# SOL_R2.net
KiCad netlist of a schematic drawn in EAGLE
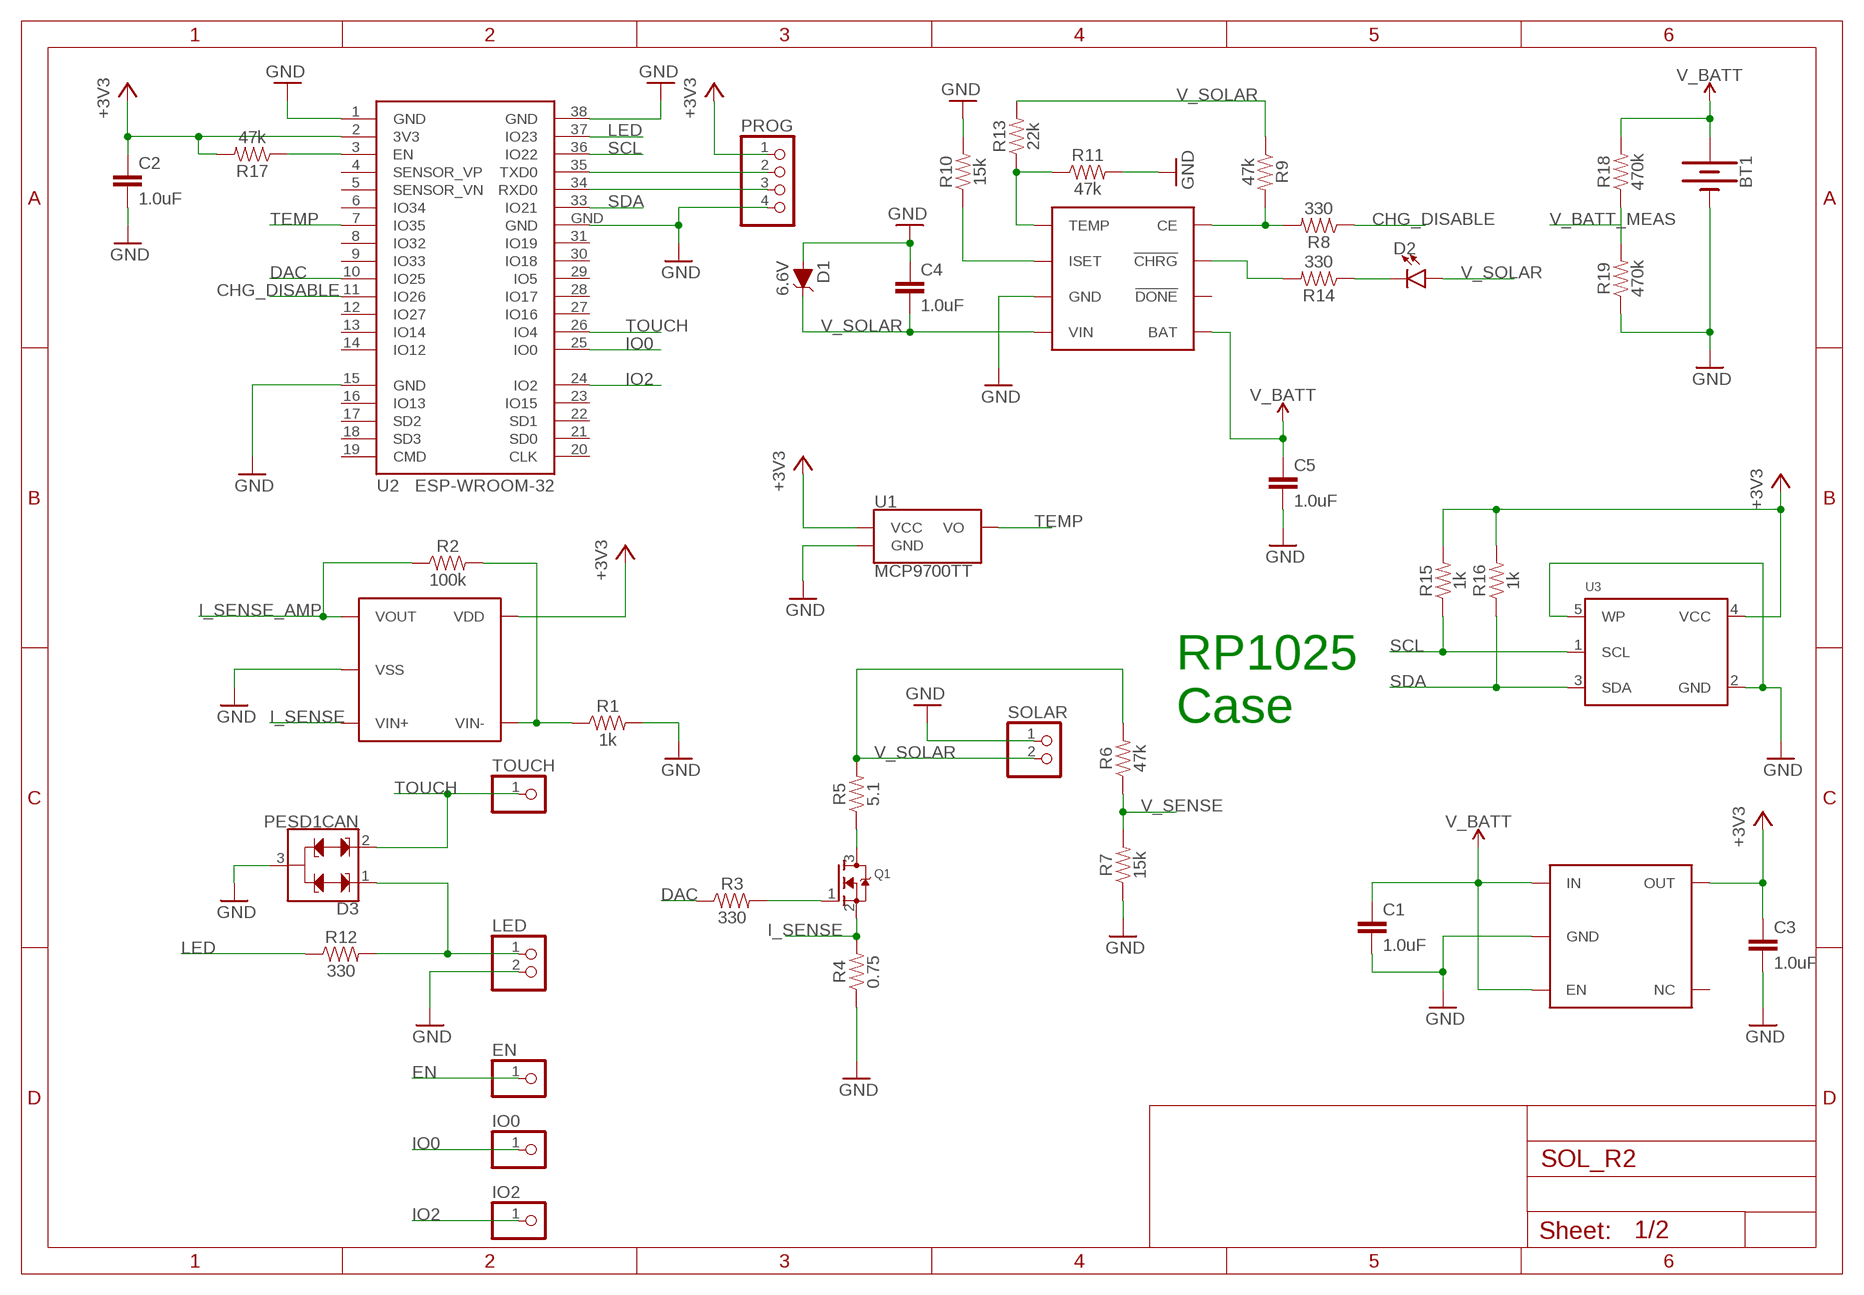
[diagram p0: schematic, sheet 1]
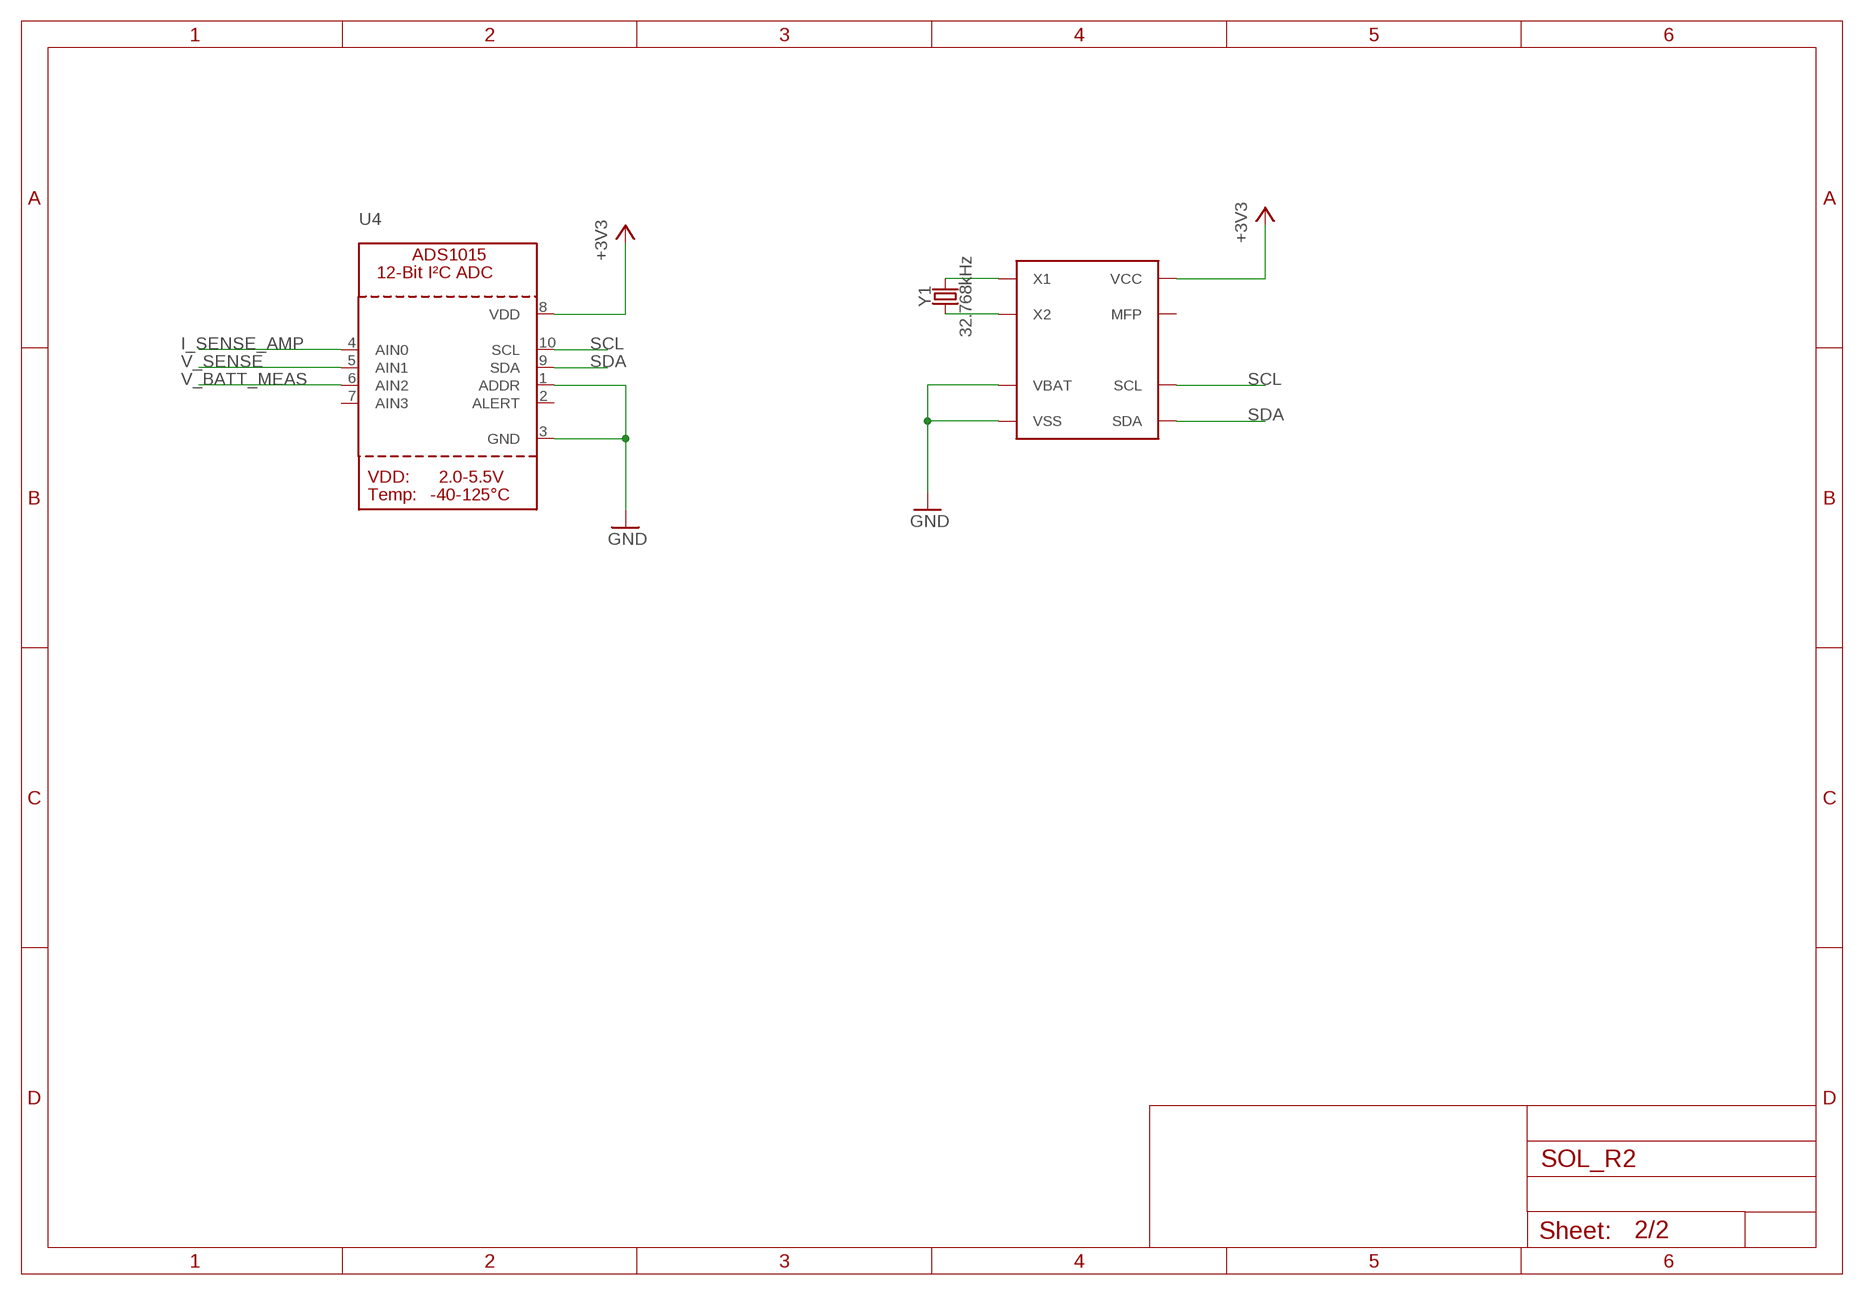
[diagram p1: schematic, sheet 2]

(export (version "E")
  (design (tool "Eeschema 10.0.6"))
  (components
    (comp (ref "U4")
      (value "ADC_ADS1015")
      (footprint "eagle-import:MSOP10")
      (libsource (lib "eagle-import") (part "ADC_ADS1015"))
    )
    (comp (ref "U8")
      (value "MCP7940")
      (footprint "eagle-import:MSOP8")
      (libsource (lib "eagle-import") (part "MCP7940"))
    )
    (comp (ref "Y1")
      (value "32.768kHz")
      (footprint "eagle-import:CRYSTAL-SMD-3.2X1.5MM")
      (libsource (lib "eagle-import") (part "CRYSTAL-32.768KHZSMD-3.2X1.5"))
    )
    (comp (ref "BT1")
      (value "BATTERY-AA")
      (footprint "eagle-import:BATTERY-AA")
      (libsource (lib "eagle-import") (part "BATTERY-AA"))
    )
    (comp (ref "C1")
      (value "1.0uF")
      (footprint "eagle-import:0805")
      (libsource (lib "eagle-import") (part "1.0UF-0805-25V-10%"))
    )
    (comp (ref "C2")
      (value "1.0uF")
      (footprint "eagle-import:0805")
      (libsource (lib "eagle-import") (part "1.0UF-0805-25V-10%"))
    )
    (comp (ref "C3")
      (value "1.0uF")
      (footprint "eagle-import:0805")
      (libsource (lib "eagle-import") (part "1.0UF-0805-25V-10%"))
    )
    (comp (ref "C4")
      (value "1.0uF")
      (footprint "eagle-import:0805")
      (libsource (lib "eagle-import") (part "1.0UF-0805-25V-10%"))
    )
    (comp (ref "C5")
      (value "1.0uF")
      (footprint "eagle-import:0805")
      (libsource (lib "eagle-import") (part "1.0UF-0805-25V-10%"))
    )
    (comp (ref "D1")
      (value "6.6V")
      (footprint "eagle-import:SOD-323")
      (libsource (lib "eagle-import") (part "DIODE-ZENER-MMSZ5232BS"))
    )
    (comp (ref "D2")
      (value "LED0603")
      (footprint "eagle-import:LED-0603")
      (libsource (lib "eagle-import") (part "LED0603"))
    )
    (comp (ref "D3")
      (value "PESD1CAN")
      (footprint "eagle-import:SOT23-3")
      (libsource (lib "eagle-import") (part "PESD1CAN"))
    )
    (comp (ref "EN")
      (value "PINHD-1X1")
      (footprint "eagle-import:1X01")
      (libsource (lib "eagle-import") (part "PINHD-1X1"))
    )
    (comp (ref "IO0")
      (value "PINHD-1X1")
      (footprint "eagle-import:1X01")
      (libsource (lib "eagle-import") (part "PINHD-1X1"))
    )
    (comp (ref "IO2")
      (value "PINHD-1X1")
      (footprint "eagle-import:1X01")
      (libsource (lib "eagle-import") (part "PINHD-1X1"))
    )
    (comp (ref "LED")
      (value "PINHD-1X2")
      (footprint "eagle-import:1X02")
      (libsource (lib "eagle-import") (part "PINHD-1X2"))
    )
    (comp (ref "PROG")
      (value "PINHD-1X4")
      (footprint "eagle-import:1X04")
      (libsource (lib "eagle-import") (part "PINHD-1X4"))
    )
    (comp (ref "Q1")
      (value "MOSFET-NREFLOW")
      (footprint "eagle-import:SOT23-R")
      (libsource (lib "eagle-import") (part "MOSFET-NREFLOW"))
    )
    (comp (ref "R1")
      (value "1k")
      (footprint "eagle-import:0603")
      (libsource (lib "eagle-import") (part "2.2KOHM-0603-1/10W-1%"))
    )
    (comp (ref "R2")
      (value "100k")
      (footprint "eagle-import:0603")
      (libsource (lib "eagle-import") (part "2.2KOHM-0603-1/10W-1%"))
    )
    (comp (ref "R3")
      (value "330")
      (footprint "eagle-import:0603")
      (libsource (lib "eagle-import") (part "2.2KOHM-0603-1/10W-1%"))
    )
    (comp (ref "R4")
      (value "0.75")
      (footprint "eagle-import:0805")
      (libsource (lib "eagle-import") (part "0.3OHM-0805-1/8W-1%"))
    )
    (comp (ref "R5")
      (value "5.1")
      (footprint "eagle-import:0603")
      (libsource (lib "eagle-import") (part "33OHM-0603-1/10W-1%"))
    )
    (comp (ref "R6")
      (value "47k")
      (footprint "eagle-import:0603")
      (libsource (lib "eagle-import") (part "47KOHM-0603-1/10W-1%"))
    )
    (comp (ref "R7")
      (value "15k")
      (footprint "eagle-import:0603")
      (libsource (lib "eagle-import") (part "15KOHM-0603-1/10W-1%"))
    )
    (comp (ref "R8")
      (value "330")
      (footprint "eagle-import:0603")
      (libsource (lib "eagle-import") (part "2.2KOHM-0603-1/10W-1%"))
    )
    (comp (ref "R9")
      (value "47k")
      (footprint "eagle-import:0603")
      (libsource (lib "eagle-import") (part "47KOHM-0603-1/10W-1%"))
    )
    (comp (ref "R10")
      (value "15k")
      (footprint "eagle-import:0603")
      (libsource (lib "eagle-import") (part "15KOHM-0603-1/10W-1%"))
    )
    (comp (ref "R11")
      (value "47k")
      (footprint "eagle-import:0603")
      (libsource (lib "eagle-import") (part "47KOHM-0603-1/10W-1%"))
    )
    (comp (ref "R12")
      (value "330")
      (footprint "eagle-import:0603")
      (libsource (lib "eagle-import") (part "2.2KOHM-0603-1/10W-1%"))
    )
    (comp (ref "R13")
      (value "22k")
      (footprint "eagle-import:0603")
      (libsource (lib "eagle-import") (part "47KOHM-0603-1/10W-1%"))
    )
    (comp (ref "R14")
      (value "330")
      (footprint "eagle-import:0603")
      (libsource (lib "eagle-import") (part "2.2KOHM-0603-1/10W-1%"))
    )
    (comp (ref "R15")
      (value "1k")
      (footprint "eagle-import:0603")
      (libsource (lib "eagle-import") (part "2.2KOHM-0603-1/10W-1%"))
    )
    (comp (ref "R16")
      (value "1k")
      (footprint "eagle-import:0603")
      (libsource (lib "eagle-import") (part "2.2KOHM-0603-1/10W-1%"))
    )
    (comp (ref "R17")
      (value "47k")
      (footprint "eagle-import:0603")
      (libsource (lib "eagle-import") (part "47KOHM-0603-1/10W-1%"))
    )
    (comp (ref "R18")
      (value "470k")
      (footprint "eagle-import:0603")
      (libsource (lib "eagle-import") (part "2.2KOHM-0603-1/10W-1%"))
    )
    (comp (ref "R19")
      (value "470k")
      (footprint "eagle-import:0603")
      (libsource (lib "eagle-import") (part "2.2KOHM-0603-1/10W-1%"))
    )
    (comp (ref "SOLAR")
      (value "PINHD-1X2")
      (footprint "eagle-import:1X02")
      (libsource (lib "eagle-import") (part "PINHD-1X2"))
    )
    (comp (ref "TOUCH")
      (value "PINHD-1X1")
      (footprint "eagle-import:1X01")
      (libsource (lib "eagle-import") (part "PINHD-1X1"))
    )
    (comp (ref "U1")
      (value "MCP9700TT")
      (footprint "eagle-import:SOT23-3")
      (libsource (lib "eagle-import") (part "MCP9700TT"))
    )
    (comp (ref "U2")
      (value "ESP-WROOM-32")
      (footprint "eagle-import:ESP-WROOM-32")
      (libsource (lib "eagle-import") (part "ESP-WROOM-32"))
    )
    (comp (ref "U3")
      (value "EEPROM_I2C_MCP24AA32")
      (footprint "eagle-import:SOT23-5")
      (libsource (lib "eagle-import") (part "EEPROM_I2C_MCP24AA32"))
    )
    (comp (ref "U5")
      (value "MCP6001")
      (footprint "eagle-import:SOT23-5L")
      (libsource (lib "eagle-import") (part "MCP6001"))
    )
    (comp (ref "U6")
      (value "TLV755")
      (footprint "eagle-import:SOT23-DBV")
      (libsource (lib "eagle-import") (part "TLV755"))
    )
    (comp (ref "U7")
      (value "DIO5158XM8")
      (footprint "eagle-import:MSOP8")
      (libsource (lib "eagle-import") (part "DIO5158XM8"))
    )
  )
  (nets
    (net (code "1") (name "+3V3") (class "Default")
      (node (ref "C2") (pin "1") (pinfunction "1_1") (pintype "passive"))
      (node (ref "C3") (pin "1") (pinfunction "1_1") (pintype "passive"))
      (node (ref "PROG") (pin "1") (pinfunction "1_1") (pintype "passive"))
      (node (ref "R15") (pin "2") (pinfunction "2_2") (pintype "passive"))
      (node (ref "R16") (pin "2") (pinfunction "2_2") (pintype "passive"))
      (node (ref "R17") (pin "2") (pinfunction "2_2") (pintype "passive"))
      (node (ref "U1") (pin "1") (pinfunction "VCC_1") (pintype "bidirectional"))
      (node (ref "U2") (pin "2") (pinfunction "3V3_2") (pintype "power_in"))
      (node (ref "U3") (pin "4") (pinfunction "VCC_4") (pintype "bidirectional"))
      (node (ref "U4") (pin "8") (pinfunction "VDD_8") (pintype "bidirectional"))
      (node (ref "U5") (pin "5") (pinfunction "VDD_5") (pintype "bidirectional"))
      (node (ref "U6") (pin "5") (pinfunction "OUT_5") (pintype "bidirectional"))
      (node (ref "U8") (pin "8") (pinfunction "VCC_8") (pintype "bidirectional"))
    )
    (net (code "2") (name "CHG_DISABLE") (class "Default")
      (node (ref "R8") (pin "1") (pinfunction "1_1") (pintype "passive"))
      (node (ref "U2") (pin "11") (pinfunction "IO26_11") (pintype "bidirectional"))
    )
    (net (code "3") (name "DAC") (class "Default")
      (node (ref "R3") (pin "1") (pinfunction "1_1") (pintype "passive"))
      (node (ref "U2") (pin "10") (pinfunction "IO25_10") (pintype "bidirectional"))
    )
    (net (code "4") (name "EN") (class "Default")
      (node (ref "EN") (pin "1") (pinfunction "1_1") (pintype "passive"))
      (node (ref "R17") (pin "1") (pinfunction "1_1") (pintype "passive"))
      (node (ref "U2") (pin "3") (pinfunction "EN_3") (pintype "input"))
    )
    (net (code "5") (name "GND") (class "Default")
      (node (ref "BT1") (pin "GND@1") (pinfunction "-_GND@1") (pintype "power_in"))
      (node (ref "C1") (pin "2") (pinfunction "2_2") (pintype "passive"))
      (node (ref "C2") (pin "2") (pinfunction "2_2") (pintype "passive"))
      (node (ref "C3") (pin "2") (pinfunction "2_2") (pintype "passive"))
      (node (ref "C4") (pin "1") (pinfunction "1_1") (pintype "passive"))
      (node (ref "C5") (pin "2") (pinfunction "2_2") (pintype "passive"))
      (node (ref "D1") (pin "A") (pinfunction "A_A") (pintype "passive"))
      (node (ref "D3") (pin "3") (pinfunction "3_3") (pintype "bidirectional"))
      (node (ref "LED") (pin "2") (pinfunction "2_2") (pintype "passive"))
      (node (ref "PROG") (pin "4") (pinfunction "4_4") (pintype "passive"))
      (node (ref "R1") (pin "2") (pinfunction "2_2") (pintype "passive"))
      (node (ref "R10") (pin "2") (pinfunction "2_2") (pintype "passive"))
      (node (ref "R11") (pin "2") (pinfunction "2_2") (pintype "passive"))
      (node (ref "R19") (pin "1") (pinfunction "1_1") (pintype "passive"))
      (node (ref "R4") (pin "1") (pinfunction "1_1") (pintype "passive"))
      (node (ref "R7") (pin "1") (pinfunction "1_1") (pintype "passive"))
      (node (ref "SOLAR") (pin "1") (pinfunction "1_1") (pintype "passive"))
      (node (ref "U1") (pin "3") (pinfunction "GND_3") (pintype "bidirectional"))
      (node (ref "U2") (pin "1") (pinfunction "GND_1") (pintype "power_in"))
      (node (ref "U2") (pin "15") (pinfunction "GND_15") (pintype "power_in"))
      (node (ref "U2") (pin "38") (pinfunction "GND_38") (pintype "power_in"))
      (node (ref "U2") (pin "GND") (pinfunction "GND_GND") (pintype "power_in"))
      (node (ref "U3") (pin "2") (pinfunction "GND_2") (pintype "bidirectional"))
      (node (ref "U3") (pin "5") (pinfunction "WP_5") (pintype "bidirectional"))
      (node (ref "U4") (pin "1") (pinfunction "ADDR_1") (pintype "bidirectional"))
      (node (ref "U4") (pin "3") (pinfunction "GND_3") (pintype "bidirectional"))
      (node (ref "U5") (pin "2") (pinfunction "VSS_2") (pintype "bidirectional"))
      (node (ref "U6") (pin "2") (pinfunction "GND_2") (pintype "bidirectional"))
      (node (ref "U7") (pin "3") (pinfunction "GND_3") (pintype "bidirectional"))
      (node (ref "U8") (pin "3") (pinfunction "VBAT_3") (pintype "bidirectional"))
      (node (ref "U8") (pin "4") (pinfunction "VSS_4") (pintype "bidirectional"))
    )
    (net (code "6") (name "IO0") (class "Default")
      (node (ref "IO0") (pin "1") (pinfunction "1_1") (pintype "passive"))
      (node (ref "U2") (pin "25") (pinfunction "IO0_25") (pintype "bidirectional"))
    )
    (net (code "7") (name "IO2") (class "Default")
      (node (ref "IO2") (pin "1") (pinfunction "1_1") (pintype "passive"))
      (node (ref "U2") (pin "24") (pinfunction "IO2_24") (pintype "bidirectional"))
    )
    (net (code "8") (name "I_SENSE") (class "Default")
      (node (ref "Q1") (pin "2") (pinfunction "S_2") (pintype "bidirectional"))
      (node (ref "R4") (pin "2") (pinfunction "2_2") (pintype "passive"))
      (node (ref "U5") (pin "3") (pinfunction "VIN+_3") (pintype "bidirectional"))
    )
    (net (code "9") (name "I_SENSE_AMP") (class "Default")
      (node (ref "R2") (pin "1") (pinfunction "1_1") (pintype "passive"))
      (node (ref "U4") (pin "4") (pinfunction "AIN0_4") (pintype "bidirectional"))
      (node (ref "U5") (pin "1") (pinfunction "VOUT_1") (pintype "bidirectional"))
    )
    (net (code "10") (name "LED") (class "Default")
      (node (ref "R12") (pin "1") (pinfunction "1_1") (pintype "passive"))
      (node (ref "U2") (pin "37") (pinfunction "IO23_37") (pintype "bidirectional"))
    )
    (net (code "11") (name "Net-(D2-PadC)") (class "Default")
      (node (ref "D2") (pin "C") (pinfunction "C_C") (pintype "passive"))
      (node (ref "R14") (pin "1") (pinfunction "1_1") (pintype "passive"))
    )
    (net (code "12") (name "Net-(D3-Pad1)") (class "Default")
      (node (ref "D3") (pin "1") (pinfunction "1_1") (pintype "bidirectional"))
      (node (ref "LED") (pin "1") (pinfunction "1_1") (pintype "passive"))
      (node (ref "R12") (pin "2") (pinfunction "2_2") (pintype "passive"))
    )
    (net (code "13") (name "Net-(Q1-D)") (class "Default")
      (node (ref "Q1") (pin "3") (pinfunction "D_3") (pintype "bidirectional"))
      (node (ref "R5") (pin "1") (pinfunction "1_1") (pintype "passive"))
    )
    (net (code "14") (name "Net-(Q1-G)") (class "Default")
      (node (ref "Q1") (pin "1") (pinfunction "G_1") (pintype "bidirectional"))
      (node (ref "R3") (pin "2") (pinfunction "2_2") (pintype "passive"))
    )
    (net (code "15") (name "Net-(U2-RXD0)") (class "Default")
      (node (ref "PROG") (pin "3") (pinfunction "3_3") (pintype "passive"))
      (node (ref "U2") (pin "34") (pinfunction "RXD0_34") (pintype "bidirectional"))
    )
    (net (code "16") (name "Net-(U2-TXD0)") (class "Default")
      (node (ref "PROG") (pin "2") (pinfunction "2_2") (pintype "passive"))
      (node (ref "U2") (pin "35") (pinfunction "TXD0_35") (pintype "bidirectional"))
    )
    (net (code "17") (name "Net-(U5-VIN-)") (class "Default")
      (node (ref "R1") (pin "1") (pinfunction "1_1") (pintype "passive"))
      (node (ref "R2") (pin "2") (pinfunction "2_2") (pintype "passive"))
      (node (ref "U5") (pin "4") (pinfunction "VIN-_4") (pintype "bidirectional"))
    )
    (net (code "18") (name "Net-(U7-CE)") (class "Default")
      (node (ref "R8") (pin "2") (pinfunction "2_2") (pintype "passive"))
      (node (ref "R9") (pin "2") (pinfunction "2_2") (pintype "passive"))
      (node (ref "U7") (pin "8") (pinfunction "CE_8") (pintype "bidirectional"))
    )
    (net (code "19") (name "Net-(U7-ISET)") (class "Default")
      (node (ref "R10") (pin "1") (pinfunction "1_1") (pintype "passive"))
      (node (ref "U7") (pin "2") (pinfunction "ISET_2") (pintype "bidirectional"))
    )
    (net (code "20") (name "Net-(U7-TEMP)") (class "Default")
      (node (ref "R11") (pin "1") (pinfunction "1_1") (pintype "passive"))
      (node (ref "R13") (pin "1") (pinfunction "1_1") (pintype "passive"))
      (node (ref "U7") (pin "1") (pinfunction "TEMP_1") (pintype "bidirectional"))
    )
    (net (code "21") (name "Net-(U7-~{CHRG})") (class "Default")
      (node (ref "R14") (pin "2") (pinfunction "2_2") (pintype "passive"))
      (node (ref "U7") (pin "7") (pinfunction "~{CHRG}_7") (pintype "bidirectional"))
    )
    (net (code "22") (name "Net-(U8-X1)") (class "Default")
      (node (ref "U8") (pin "1") (pinfunction "X1_1") (pintype "bidirectional"))
      (node (ref "Y1") (pin "P$2") (pinfunction "2_P$2") (pintype "passive"))
    )
    (net (code "23") (name "Net-(U8-X2)") (class "Default")
      (node (ref "U8") (pin "2") (pinfunction "X2_2") (pintype "bidirectional"))
      (node (ref "Y1") (pin "P$1") (pinfunction "1_P$1") (pintype "passive"))
    )
    (net (code "24") (name "SCL") (class "Default")
      (node (ref "R15") (pin "1") (pinfunction "1_1") (pintype "passive"))
      (node (ref "U2") (pin "36") (pinfunction "IO22_36") (pintype "bidirectional"))
      (node (ref "U3") (pin "1") (pinfunction "SCL_1") (pintype "bidirectional"))
      (node (ref "U4") (pin "10") (pinfunction "SCL_10") (pintype "bidirectional"))
      (node (ref "U8") (pin "6") (pinfunction "SCL_6") (pintype "bidirectional"))
    )
    (net (code "25") (name "SDA") (class "Default")
      (node (ref "R16") (pin "1") (pinfunction "1_1") (pintype "passive"))
      (node (ref "U2") (pin "33") (pinfunction "IO21_33") (pintype "bidirectional"))
      (node (ref "U3") (pin "3") (pinfunction "SDA_3") (pintype "bidirectional"))
      (node (ref "U4") (pin "9") (pinfunction "SDA_9") (pintype "bidirectional"))
      (node (ref "U8") (pin "5") (pinfunction "SDA_5") (pintype "bidirectional"))
    )
    (net (code "26") (name "TEMP") (class "Default")
      (node (ref "U1") (pin "2") (pinfunction "VO_2") (pintype "bidirectional"))
      (node (ref "U2") (pin "7") (pinfunction "IO35_7") (pintype "bidirectional"))
    )
    (net (code "27") (name "TOUCH") (class "Default")
      (node (ref "D3") (pin "2") (pinfunction "2_2") (pintype "bidirectional"))
      (node (ref "TOUCH") (pin "1") (pinfunction "1_1") (pintype "passive"))
      (node (ref "U2") (pin "26") (pinfunction "IO4_26") (pintype "bidirectional"))
    )
    (net (code "28") (name "V_BATT") (class "Default")
      (node (ref "BT1") (pin "PWR@1") (pinfunction "+_PWR@1") (pintype "power_in"))
      (node (ref "C1") (pin "1") (pinfunction "1_1") (pintype "passive"))
      (node (ref "C5") (pin "1") (pinfunction "1_1") (pintype "passive"))
      (node (ref "R18") (pin "2") (pinfunction "2_2") (pintype "passive"))
      (node (ref "U6") (pin "1") (pinfunction "IN_1") (pintype "bidirectional"))
      (node (ref "U6") (pin "3") (pinfunction "EN_3") (pintype "bidirectional"))
      (node (ref "U7") (pin "5") (pinfunction "BAT_5") (pintype "bidirectional"))
    )
    (net (code "29") (name "V_BATT_MEAS") (class "Default")
      (node (ref "R18") (pin "1") (pinfunction "1_1") (pintype "passive"))
      (node (ref "R19") (pin "2") (pinfunction "2_2") (pintype "passive"))
      (node (ref "U4") (pin "6") (pinfunction "AIN2_6") (pintype "bidirectional"))
    )
    (net (code "30") (name "V_SENSE") (class "Default")
      (node (ref "R6") (pin "1") (pinfunction "1_1") (pintype "passive"))
      (node (ref "R7") (pin "2") (pinfunction "2_2") (pintype "passive"))
      (node (ref "U4") (pin "5") (pinfunction "AIN1_5") (pintype "bidirectional"))
    )
    (net (code "31") (name "V_SOLAR") (class "Default")
      (node (ref "C4") (pin "2") (pinfunction "2_2") (pintype "passive"))
      (node (ref "D1") (pin "C") (pinfunction "C_C") (pintype "passive"))
      (node (ref "D2") (pin "A") (pinfunction "A_A") (pintype "passive"))
      (node (ref "R13") (pin "2") (pinfunction "2_2") (pintype "passive"))
      (node (ref "R5") (pin "2") (pinfunction "2_2") (pintype "passive"))
      (node (ref "R6") (pin "2") (pinfunction "2_2") (pintype "passive"))
      (node (ref "R9") (pin "1") (pinfunction "1_1") (pintype "passive"))
      (node (ref "SOLAR") (pin "2") (pinfunction "2_2") (pintype "passive"))
      (node (ref "U7") (pin "4") (pinfunction "VIN_4") (pintype "bidirectional"))
    )
    (net (code "32") (name "unconnected-(U2-CLK-Pad20)") (class "Default")
      (node (ref "U2") (pin "20") (pinfunction "CLK_20") (pintype "bidirectional"))
    )
    (net (code "33") (name "unconnected-(U2-CMD-Pad19)") (class "Default")
      (node (ref "U2") (pin "19") (pinfunction "CMD_19") (pintype "bidirectional"))
    )
    (net (code "34") (name "unconnected-(U2-IO5-Pad29)") (class "Default")
      (node (ref "U2") (pin "29") (pinfunction "IO5_29") (pintype "bidirectional"))
    )
    (net (code "35") (name "unconnected-(U2-IO12-Pad14)") (class "Default")
      (node (ref "U2") (pin "14") (pinfunction "IO12_14") (pintype "bidirectional"))
    )
    (net (code "36") (name "unconnected-(U2-IO13-Pad16)") (class "Default")
      (node (ref "U2") (pin "16") (pinfunction "IO13_16") (pintype "bidirectional"))
    )
    (net (code "37") (name "unconnected-(U2-IO14-Pad13)") (class "Default")
      (node (ref "U2") (pin "13") (pinfunction "IO14_13") (pintype "bidirectional"))
    )
    (net (code "38") (name "unconnected-(U2-IO15-Pad23)") (class "Default")
      (node (ref "U2") (pin "23") (pinfunction "IO15_23") (pintype "bidirectional"))
    )
    (net (code "39") (name "unconnected-(U2-IO16-Pad27)") (class "Default")
      (node (ref "U2") (pin "27") (pinfunction "IO16_27") (pintype "bidirectional"))
    )
    (net (code "40") (name "unconnected-(U2-IO17-Pad28)") (class "Default")
      (node (ref "U2") (pin "28") (pinfunction "IO17_28") (pintype "bidirectional"))
    )
    (net (code "41") (name "unconnected-(U2-IO18-Pad30)") (class "Default")
      (node (ref "U2") (pin "30") (pinfunction "IO18_30") (pintype "bidirectional"))
    )
    (net (code "42") (name "unconnected-(U2-IO19-Pad31)") (class "Default")
      (node (ref "U2") (pin "31") (pinfunction "IO19_31") (pintype "bidirectional"))
    )
    (net (code "43") (name "unconnected-(U2-IO27-Pad12)") (class "Default")
      (node (ref "U2") (pin "12") (pinfunction "IO27_12") (pintype "bidirectional"))
    )
    (net (code "44") (name "unconnected-(U2-IO32-Pad8)") (class "Default")
      (node (ref "U2") (pin "8") (pinfunction "IO32_8") (pintype "bidirectional"))
    )
    (net (code "45") (name "unconnected-(U2-IO33-Pad9)") (class "Default")
      (node (ref "U2") (pin "9") (pinfunction "IO33_9") (pintype "bidirectional"))
    )
    (net (code "46") (name "unconnected-(U2-IO34-Pad6)") (class "Default")
      (node (ref "U2") (pin "6") (pinfunction "IO34_6") (pintype "bidirectional"))
    )
    (net (code "47") (name "unconnected-(U2-SD0-Pad21)") (class "Default")
      (node (ref "U2") (pin "21") (pinfunction "SD0_21") (pintype "bidirectional"))
    )
    (net (code "48") (name "unconnected-(U2-SD1-Pad22)") (class "Default")
      (node (ref "U2") (pin "22") (pinfunction "SD1_22") (pintype "bidirectional"))
    )
    (net (code "49") (name "unconnected-(U2-SD2-Pad17)") (class "Default")
      (node (ref "U2") (pin "17") (pinfunction "SD2_17") (pintype "bidirectional"))
    )
    (net (code "50") (name "unconnected-(U2-SD3-Pad18)") (class "Default")
      (node (ref "U2") (pin "18") (pinfunction "SD3_18") (pintype "bidirectional"))
    )
    (net (code "51") (name "unconnected-(U2-SENSOR_VN-Pad5)") (class "Default")
      (node (ref "U2") (pin "5") (pinfunction "SENSOR_VN_5") (pintype "bidirectional"))
    )
    (net (code "52") (name "unconnected-(U2-SENSOR_VP-Pad4)") (class "Default")
      (node (ref "U2") (pin "4") (pinfunction "SENSOR_VP_4") (pintype "bidirectional"))
    )
    (net (code "53") (name "unconnected-(U4-AIN3-Pad7)") (class "Default")
      (node (ref "U4") (pin "7") (pinfunction "AIN3_7") (pintype "bidirectional"))
    )
    (net (code "54") (name "unconnected-(U4-ALERT-Pad2)") (class "Default")
      (node (ref "U4") (pin "2") (pinfunction "ALERT_2") (pintype "bidirectional"))
    )
    (net (code "55") (name "unconnected-(U6-NC-Pad4)") (class "Default")
      (node (ref "U6") (pin "4") (pinfunction "NC_4") (pintype "bidirectional"))
    )
    (net (code "56") (name "unconnected-(U7-~{DONE}-Pad6)") (class "Default")
      (node (ref "U7") (pin "6") (pinfunction "~{DONE}_6") (pintype "bidirectional"))
    )
    (net (code "57") (name "unconnected-(U8-MFP-Pad7)") (class "Default")
      (node (ref "U8") (pin "7") (pinfunction "MFP_7") (pintype "bidirectional"))
    )
  )
)
